# SCH_HallcurrentLA25p.net
KiCad netlist of a schematic drawn in Altium Designer
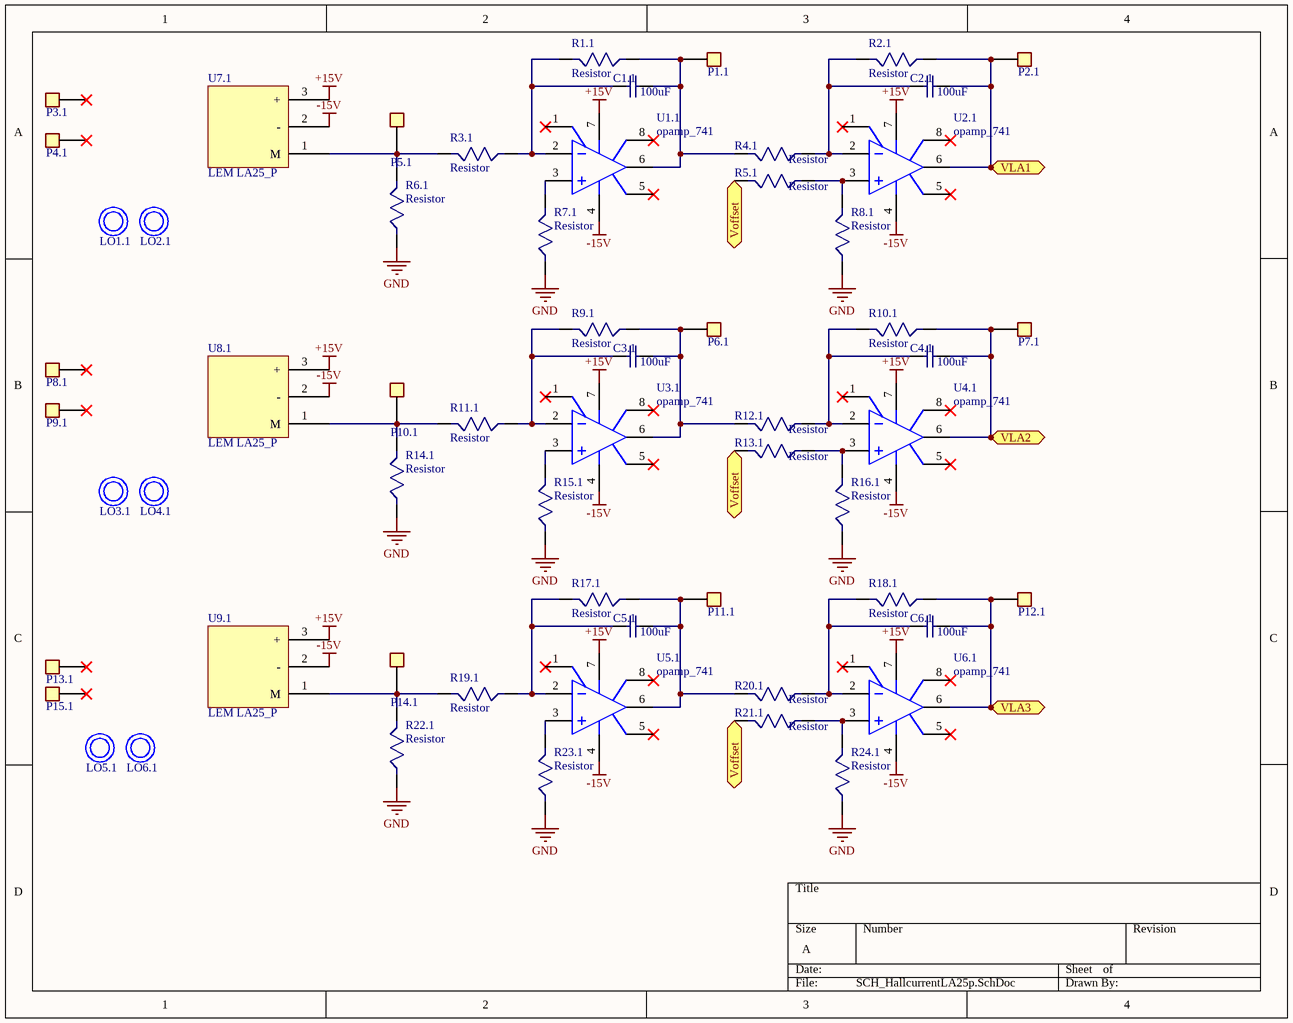
[diagram p0: SCH_HallcurrentLA25p.SchDoc]

(export (version "E")
  (design (tool "Eeschema 10.0.6"))
  (components
    (comp (ref "C1.1")
      (value "100uF")
      (footprint "CAPC0805")
      (description "capacitor non polar")
      (libsource (lib "thuvien_altium") (part "capacitor_non_polar"))
    )
    (comp (ref "C2.1")
      (value "100uF")
      (footprint "CAPC0805")
      (description "capacitor non polar")
      (libsource (lib "thuvien_altium") (part "capacitor_non_polar"))
    )
    (comp (ref "C3.1")
      (value "100uF")
      (footprint "CAPC0805")
      (description "capacitor non polar")
      (libsource (lib "thuvien_altium") (part "capacitor_non_polar"))
    )
    (comp (ref "C4.1")
      (value "100uF")
      (footprint "CAPC0805")
      (description "capacitor non polar")
      (libsource (lib "thuvien_altium") (part "capacitor_non_polar"))
    )
    (comp (ref "C5.1")
      (value "100uF")
      (footprint "CAPC0805")
      (description "capacitor non polar")
      (libsource (lib "thuvien_altium") (part "capacitor_non_polar"))
    )
    (comp (ref "C6.1")
      (value "100uF")
      (footprint "CAPC0805")
      (description "capacitor non polar")
      (libsource (lib "thuvien_altium") (part "capacitor_non_polar"))
    )
    (comp (ref "LO1.1")
      (value "LO KHOAN")
      (footprint "thuvien_altium:Lo Khoang - 6mm")
      (libsource (lib "thuvien_altium") (part "LO KHOAN"))
    )
    (comp (ref "LO2.1")
      (value "LO KHOAN")
      (footprint "thuvien_altium:Lo Khoang - 6mm")
      (libsource (lib "thuvien_altium") (part "LO KHOAN"))
    )
    (comp (ref "LO3.1")
      (value "LO KHOAN")
      (footprint "thuvien_altium:Lo Khoang - 6mm")
      (libsource (lib "thuvien_altium") (part "LO KHOAN"))
    )
    (comp (ref "LO4.1")
      (value "LO KHOAN")
      (footprint "thuvien_altium:Lo Khoang - 6mm")
      (libsource (lib "thuvien_altium") (part "LO KHOAN"))
    )
    (comp (ref "LO5.1")
      (value "LO KHOAN")
      (footprint "thuvien_altium:Lo Khoang - 6mm")
      (libsource (lib "thuvien_altium") (part "LO KHOAN"))
    )
    (comp (ref "LO6.1")
      (value "LO KHOAN")
      (footprint "thuvien_altium:Lo Khoang - 6mm")
      (libsource (lib "thuvien_altium") (part "LO KHOAN"))
    )
    (comp (ref "P1.1")
      (value "testpin")
      (footprint "thuvien_altium:Tp_blue_1p")
      (libsource (lib "thuvien_altium") (part "testpin"))
    )
    (comp (ref "P2.1")
      (value "testpin")
      (footprint "thuvien_altium:Tp_blue_1p")
      (libsource (lib "thuvien_altium") (part "testpin"))
    )
    (comp (ref "P3.1")
      (value "Terminal on PCB")
      (footprint "thuvien_altium:Terminal M5")
      (libsource (lib "thuvien_altium") (part "Terminal on PCB"))
    )
    (comp (ref "P4.1")
      (value "Terminal on PCB")
      (footprint "thuvien_altium:Terminal M5")
      (libsource (lib "thuvien_altium") (part "Terminal on PCB"))
    )
    (comp (ref "P5.1")
      (value "testpin")
      (footprint "thuvien_altium:Tp_blue_1p")
      (libsource (lib "") (part "testpin_1"))
    )
    (comp (ref "P6.1")
      (value "testpin")
      (footprint "thuvien_altium:Tp_blue_1p")
      (libsource (lib "thuvien_altium") (part "testpin"))
    )
    (comp (ref "P7.1")
      (value "testpin")
      (footprint "thuvien_altium:Tp_blue_1p")
      (libsource (lib "thuvien_altium") (part "testpin"))
    )
    (comp (ref "P8.1")
      (value "Terminal on PCB")
      (footprint "thuvien_altium:Terminal M5")
      (libsource (lib "thuvien_altium") (part "Terminal on PCB"))
    )
    (comp (ref "P9.1")
      (value "Terminal on PCB")
      (footprint "thuvien_altium:Terminal M5")
      (libsource (lib "thuvien_altium") (part "Terminal on PCB"))
    )
    (comp (ref "P10.1")
      (value "testpin")
      (footprint "thuvien_altium:Tp_blue_1p")
      (libsource (lib "") (part "testpin_1"))
    )
    (comp (ref "P11.1")
      (value "testpin")
      (footprint "thuvien_altium:Tp_blue_1p")
      (libsource (lib "thuvien_altium") (part "testpin"))
    )
    (comp (ref "P12.1")
      (value "testpin")
      (footprint "thuvien_altium:Tp_blue_1p")
      (libsource (lib "thuvien_altium") (part "testpin"))
    )
    (comp (ref "P13.1")
      (value "Terminal on PCB")
      (footprint "thuvien_altium:Terminal M5")
      (libsource (lib "thuvien_altium") (part "Terminal on PCB"))
    )
    (comp (ref "P14.1")
      (value "testpin")
      (footprint "thuvien_altium:Tp_blue_1p")
      (libsource (lib "") (part "testpin_1"))
    )
    (comp (ref "P15.1")
      (value "Terminal on PCB")
      (footprint "thuvien_altium:Terminal M5")
      (libsource (lib "thuvien_altium") (part "Terminal on PCB"))
    )
    (comp (ref "R1.1")
      (value "Resistor")
      (footprint "RESC0805")
      (description "resistor")
      (libsource (lib "thuvien_altium") (part "resistor"))
    )
    (comp (ref "R2.1")
      (value "Resistor")
      (footprint "RESC0805")
      (description "resistor")
      (libsource (lib "thuvien_altium") (part "resistor"))
    )
    (comp (ref "R3.1")
      (value "Resistor")
      (footprint "RESC0805")
      (description "resistor")
      (libsource (lib "thuvien_altium") (part "resistor"))
    )
    (comp (ref "R4.1")
      (value "Resistor")
      (footprint "RESC0805")
      (description "resistor")
      (libsource (lib "thuvien_altium") (part "resistor"))
    )
    (comp (ref "R5.1")
      (value "Resistor")
      (footprint "RESC0805")
      (description "resistor")
      (libsource (lib "thuvien_altium") (part "resistor"))
    )
    (comp (ref "R6.1")
      (value "Resistor")
      (footprint "RESC0805")
      (description "resistor")
      (libsource (lib "thuvien_altium") (part "resistor"))
    )
    (comp (ref "R7.1")
      (value "Resistor")
      (footprint "RESC0805")
      (description "resistor")
      (libsource (lib "thuvien_altium") (part "resistor"))
    )
    (comp (ref "R8.1")
      (value "Resistor")
      (footprint "RESC0805")
      (description "resistor")
      (libsource (lib "thuvien_altium") (part "resistor"))
    )
    (comp (ref "R9.1")
      (value "Resistor")
      (footprint "RESC0805")
      (description "resistor")
      (libsource (lib "thuvien_altium") (part "resistor"))
    )
    (comp (ref "R10.1")
      (value "Resistor")
      (footprint "RESC0805")
      (description "resistor")
      (libsource (lib "thuvien_altium") (part "resistor"))
    )
    (comp (ref "R11.1")
      (value "Resistor")
      (footprint "RESC0805")
      (description "resistor")
      (libsource (lib "thuvien_altium") (part "resistor"))
    )
    (comp (ref "R12.1")
      (value "Resistor")
      (footprint "RESC0805")
      (description "resistor")
      (libsource (lib "thuvien_altium") (part "resistor"))
    )
    (comp (ref "R13.1")
      (value "Resistor")
      (footprint "RESC0805")
      (description "resistor")
      (libsource (lib "thuvien_altium") (part "resistor"))
    )
    (comp (ref "R14.1")
      (value "Resistor")
      (footprint "RESC0805")
      (description "resistor")
      (libsource (lib "thuvien_altium") (part "resistor"))
    )
    (comp (ref "R15.1")
      (value "Resistor")
      (footprint "RESC0805")
      (description "resistor")
      (libsource (lib "thuvien_altium") (part "resistor"))
    )
    (comp (ref "R16.1")
      (value "Resistor")
      (footprint "RESC0805")
      (description "resistor")
      (libsource (lib "thuvien_altium") (part "resistor"))
    )
    (comp (ref "R17.1")
      (value "Resistor")
      (footprint "RESC0805")
      (description "resistor")
      (libsource (lib "thuvien_altium") (part "resistor"))
    )
    (comp (ref "R18.1")
      (value "Resistor")
      (footprint "RESC0805")
      (description "resistor")
      (libsource (lib "thuvien_altium") (part "resistor"))
    )
    (comp (ref "R19.1")
      (value "Resistor")
      (footprint "RESC0805")
      (description "resistor")
      (libsource (lib "thuvien_altium") (part "resistor"))
    )
    (comp (ref "R20.1")
      (value "Resistor")
      (footprint "RESC0805")
      (description "resistor")
      (libsource (lib "thuvien_altium") (part "resistor"))
    )
    (comp (ref "R21.1")
      (value "Resistor")
      (footprint "RESC0805")
      (description "resistor")
      (libsource (lib "thuvien_altium") (part "resistor"))
    )
    (comp (ref "R22.1")
      (value "Resistor")
      (footprint "RESC0805")
      (description "resistor")
      (libsource (lib "thuvien_altium") (part "resistor"))
    )
    (comp (ref "R23.1")
      (value "Resistor")
      (footprint "RESC0805")
      (description "resistor")
      (libsource (lib "thuvien_altium") (part "resistor"))
    )
    (comp (ref "R24.1")
      (value "Resistor")
      (footprint "RESC0805")
      (description "resistor")
      (libsource (lib "thuvien_altium") (part "resistor"))
    )
    (comp (ref "U1.1")
      (value "opamp_741")
      (footprint "thuvien_altium:SOIC-8_dan")
      (libsource (lib "thuvien_altium") (part "opamp 741"))
    )
    (comp (ref "U2.1")
      (value "opamp_741")
      (footprint "thuvien_altium:SOIC-8_dan")
      (libsource (lib "thuvien_altium") (part "opamp 741"))
    )
    (comp (ref "U3.1")
      (value "opamp_741")
      (footprint "thuvien_altium:SOIC-8_dan")
      (libsource (lib "thuvien_altium") (part "opamp 741"))
    )
    (comp (ref "U4.1")
      (value "opamp_741")
      (footprint "thuvien_altium:SOIC-8_dan")
      (libsource (lib "thuvien_altium") (part "opamp 741"))
    )
    (comp (ref "U5.1")
      (value "opamp_741")
      (footprint "thuvien_altium:SOIC-8_dan")
      (libsource (lib "thuvien_altium") (part "opamp 741"))
    )
    (comp (ref "U6.1")
      (value "opamp_741")
      (footprint "thuvien_altium:SOIC-8_dan")
      (libsource (lib "thuvien_altium") (part "opamp 741"))
    )
    (comp (ref "U7.1")
      (value "LEM LA25_P")
      (footprint "thuvien_altium:LEM LA25_P")
      (libsource (lib "thuvien_altium") (part "LEM LA25_P"))
    )
    (comp (ref "U8.1")
      (value "LEM LA25_P")
      (footprint "thuvien_altium:LEM LA25_P")
      (libsource (lib "thuvien_altium") (part "LEM LA25_P"))
    )
    (comp (ref "U9.1")
      (value "LEM LA25_P")
      (footprint "thuvien_altium:LEM LA25_P")
      (libsource (lib "thuvien_altium") (part "LEM LA25_P"))
    )
  )
  (nets
    (net (code "1") (name "+15V") (class "Default")
      (node (ref "U1.1") (pin "7") (pinfunction "V+_7") (pintype "power_in"))
      (node (ref "U2.1") (pin "7") (pinfunction "V+_7") (pintype "power_in"))
      (node (ref "U3.1") (pin "7") (pinfunction "V+_7") (pintype "power_in"))
      (node (ref "U4.1") (pin "7") (pinfunction "V+_7") (pintype "power_in"))
      (node (ref "U5.1") (pin "7") (pinfunction "V+_7") (pintype "power_in"))
      (node (ref "U6.1") (pin "7") (pinfunction "V+_7") (pintype "power_in"))
      (node (ref "U7.1") (pin "3") (pinfunction "+_3") (pintype "passive"))
      (node (ref "U8.1") (pin "3") (pinfunction "+_3") (pintype "passive"))
      (node (ref "U9.1") (pin "3") (pinfunction "+_3") (pintype "passive"))
    )
    (net (code "2") (name "-15V") (class "Default")
      (node (ref "U1.1") (pin "4") (pinfunction "V-_4") (pintype "power_in"))
      (node (ref "U2.1") (pin "4") (pinfunction "V-_4") (pintype "power_in"))
      (node (ref "U3.1") (pin "4") (pinfunction "V-_4") (pintype "power_in"))
      (node (ref "U4.1") (pin "4") (pinfunction "V-_4") (pintype "power_in"))
      (node (ref "U5.1") (pin "4") (pinfunction "V-_4") (pintype "power_in"))
      (node (ref "U6.1") (pin "4") (pinfunction "V-_4") (pintype "power_in"))
      (node (ref "U7.1") (pin "2") (pinfunction "-_2") (pintype "passive"))
      (node (ref "U8.1") (pin "2") (pinfunction "-_2") (pintype "passive"))
      (node (ref "U9.1") (pin "2") (pinfunction "-_2") (pintype "passive"))
    )
    (net (code "3") (name "/VLA1") (class "Default")
      (node (ref "C2.1") (pin "2") (pinfunction "2_2") (pintype "power_in"))
      (node (ref "P2.1") (pin "1") (pinfunction "1_1") (pintype "power_in"))
      (node (ref "R2.1") (pin "1") (pinfunction "1_1") (pintype "power_in"))
      (node (ref "U2.1") (pin "6") (pinfunction "OUT_6") (pintype "power_in"))
    )
    (net (code "4") (name "/VLA2") (class "Default")
      (node (ref "C4.1") (pin "2") (pinfunction "2_2") (pintype "power_in"))
      (node (ref "P7.1") (pin "1") (pinfunction "1_1") (pintype "power_in"))
      (node (ref "R10.1") (pin "1") (pinfunction "1_1") (pintype "power_in"))
      (node (ref "U4.1") (pin "6") (pinfunction "OUT_6") (pintype "power_in"))
    )
    (net (code "5") (name "/VLA3") (class "Default")
      (node (ref "C6.1") (pin "2") (pinfunction "2_2") (pintype "power_in"))
      (node (ref "P12.1") (pin "1") (pinfunction "1_1") (pintype "power_in"))
      (node (ref "R18.1") (pin "1") (pinfunction "1_1") (pintype "power_in"))
      (node (ref "U6.1") (pin "6") (pinfunction "OUT_6") (pintype "power_in"))
    )
    (net (code "6") (name "/Voffset") (class "Default")
      (node (ref "R13.1") (pin "2") (pinfunction "2_2") (pintype "power_in"))
      (node (ref "R21.1") (pin "2") (pinfunction "2_2") (pintype "power_in"))
      (node (ref "R5.1") (pin "2") (pinfunction "2_2") (pintype "power_in"))
    )
    (net (code "7") (name "GND") (class "Default")
      (node (ref "R14.1") (pin "1") (pinfunction "1_1") (pintype "power_in"))
      (node (ref "R15.1") (pin "1") (pinfunction "1_1") (pintype "power_in"))
      (node (ref "R16.1") (pin "1") (pinfunction "1_1") (pintype "power_in"))
      (node (ref "R22.1") (pin "1") (pinfunction "1_1") (pintype "power_in"))
      (node (ref "R23.1") (pin "1") (pinfunction "1_1") (pintype "power_in"))
      (node (ref "R24.1") (pin "1") (pinfunction "1_1") (pintype "power_in"))
      (node (ref "R6.1") (pin "1") (pinfunction "1_1") (pintype "power_in"))
      (node (ref "R7.1") (pin "1") (pinfunction "1_1") (pintype "power_in"))
      (node (ref "R8.1") (pin "1") (pinfunction "1_1") (pintype "power_in"))
    )
    (net (code "8") (name "Net-(U1.1-IN+)") (class "Default")
      (node (ref "R7.1") (pin "2") (pinfunction "2_2") (pintype "power_in"))
      (node (ref "U1.1") (pin "3") (pinfunction "IN+_3") (pintype "power_in"))
    )
    (net (code "9") (name "Net-(U1.1-IN-)") (class "Default")
      (node (ref "C1.1") (pin "1") (pinfunction "1_1") (pintype "power_in"))
      (node (ref "R1.1") (pin "2") (pinfunction "2_2") (pintype "power_in"))
      (node (ref "R3.1") (pin "1") (pinfunction "1_1") (pintype "power_in"))
      (node (ref "U1.1") (pin "2") (pinfunction "IN-_2") (pintype "power_in"))
    )
    (net (code "10") (name "Net-(U1.1-OUT)") (class "Default")
      (node (ref "C1.1") (pin "2") (pinfunction "2_2") (pintype "power_in"))
      (node (ref "P1.1") (pin "1") (pinfunction "1_1") (pintype "power_in"))
      (node (ref "R1.1") (pin "1") (pinfunction "1_1") (pintype "power_in"))
      (node (ref "R4.1") (pin "2") (pinfunction "2_2") (pintype "power_in"))
      (node (ref "U1.1") (pin "6") (pinfunction "OUT_6") (pintype "power_in"))
    )
    (net (code "11") (name "Net-(U2.1-IN+)") (class "Default")
      (node (ref "R5.1") (pin "1") (pinfunction "1_1") (pintype "power_in"))
      (node (ref "R8.1") (pin "2") (pinfunction "2_2") (pintype "power_in"))
      (node (ref "U2.1") (pin "3") (pinfunction "IN+_3") (pintype "power_in"))
    )
    (net (code "12") (name "Net-(U2.1-IN-)") (class "Default")
      (node (ref "C2.1") (pin "1") (pinfunction "1_1") (pintype "power_in"))
      (node (ref "R2.1") (pin "2") (pinfunction "2_2") (pintype "power_in"))
      (node (ref "R4.1") (pin "1") (pinfunction "1_1") (pintype "power_in"))
      (node (ref "U2.1") (pin "2") (pinfunction "IN-_2") (pintype "power_in"))
    )
    (net (code "13") (name "Net-(U3.1-IN+)") (class "Default")
      (node (ref "R15.1") (pin "2") (pinfunction "2_2") (pintype "power_in"))
      (node (ref "U3.1") (pin "3") (pinfunction "IN+_3") (pintype "power_in"))
    )
    (net (code "14") (name "Net-(U3.1-IN-)") (class "Default")
      (node (ref "C3.1") (pin "1") (pinfunction "1_1") (pintype "power_in"))
      (node (ref "R11.1") (pin "1") (pinfunction "1_1") (pintype "power_in"))
      (node (ref "R9.1") (pin "2") (pinfunction "2_2") (pintype "power_in"))
      (node (ref "U3.1") (pin "2") (pinfunction "IN-_2") (pintype "power_in"))
    )
    (net (code "15") (name "Net-(U3.1-OUT)") (class "Default")
      (node (ref "C3.1") (pin "2") (pinfunction "2_2") (pintype "power_in"))
      (node (ref "P6.1") (pin "1") (pinfunction "1_1") (pintype "power_in"))
      (node (ref "R12.1") (pin "2") (pinfunction "2_2") (pintype "power_in"))
      (node (ref "R9.1") (pin "1") (pinfunction "1_1") (pintype "power_in"))
      (node (ref "U3.1") (pin "6") (pinfunction "OUT_6") (pintype "power_in"))
    )
    (net (code "16") (name "Net-(U4.1-IN+)") (class "Default")
      (node (ref "R13.1") (pin "1") (pinfunction "1_1") (pintype "power_in"))
      (node (ref "R16.1") (pin "2") (pinfunction "2_2") (pintype "power_in"))
      (node (ref "U4.1") (pin "3") (pinfunction "IN+_3") (pintype "power_in"))
    )
    (net (code "17") (name "Net-(U4.1-IN-)") (class "Default")
      (node (ref "C4.1") (pin "1") (pinfunction "1_1") (pintype "power_in"))
      (node (ref "R10.1") (pin "2") (pinfunction "2_2") (pintype "power_in"))
      (node (ref "R12.1") (pin "1") (pinfunction "1_1") (pintype "power_in"))
      (node (ref "U4.1") (pin "2") (pinfunction "IN-_2") (pintype "power_in"))
    )
    (net (code "18") (name "Net-(U5.1-IN+)") (class "Default")
      (node (ref "R23.1") (pin "2") (pinfunction "2_2") (pintype "power_in"))
      (node (ref "U5.1") (pin "3") (pinfunction "IN+_3") (pintype "power_in"))
    )
    (net (code "19") (name "Net-(U5.1-IN-)") (class "Default")
      (node (ref "C5.1") (pin "1") (pinfunction "1_1") (pintype "power_in"))
      (node (ref "R17.1") (pin "2") (pinfunction "2_2") (pintype "power_in"))
      (node (ref "R19.1") (pin "1") (pinfunction "1_1") (pintype "power_in"))
      (node (ref "U5.1") (pin "2") (pinfunction "IN-_2") (pintype "power_in"))
    )
    (net (code "20") (name "Net-(U5.1-OUT)") (class "Default")
      (node (ref "C5.1") (pin "2") (pinfunction "2_2") (pintype "power_in"))
      (node (ref "P11.1") (pin "1") (pinfunction "1_1") (pintype "power_in"))
      (node (ref "R17.1") (pin "1") (pinfunction "1_1") (pintype "power_in"))
      (node (ref "R20.1") (pin "2") (pinfunction "2_2") (pintype "power_in"))
      (node (ref "U5.1") (pin "6") (pinfunction "OUT_6") (pintype "power_in"))
    )
    (net (code "21") (name "Net-(U6.1-IN+)") (class "Default")
      (node (ref "R21.1") (pin "1") (pinfunction "1_1") (pintype "power_in"))
      (node (ref "R24.1") (pin "2") (pinfunction "2_2") (pintype "power_in"))
      (node (ref "U6.1") (pin "3") (pinfunction "IN+_3") (pintype "power_in"))
    )
    (net (code "22") (name "Net-(U6.1-IN-)") (class "Default")
      (node (ref "C6.1") (pin "1") (pinfunction "1_1") (pintype "power_in"))
      (node (ref "R18.1") (pin "2") (pinfunction "2_2") (pintype "power_in"))
      (node (ref "R20.1") (pin "1") (pinfunction "1_1") (pintype "power_in"))
      (node (ref "U6.1") (pin "2") (pinfunction "IN-_2") (pintype "power_in"))
    )
    (net (code "23") (name "Net-(U7.1-M)") (class "Default")
      (node (ref "P5.1") (pin "1") (pinfunction "1_1") (pintype "power_in"))
      (node (ref "R3.1") (pin "2") (pinfunction "2_2") (pintype "power_in"))
      (node (ref "R6.1") (pin "2") (pinfunction "2_2") (pintype "power_in"))
      (node (ref "U7.1") (pin "1") (pinfunction "M_1") (pintype "passive"))
    )
    (net (code "24") (name "Net-(U8.1-M)") (class "Default")
      (node (ref "P10.1") (pin "1") (pinfunction "1_1") (pintype "power_in"))
      (node (ref "R11.1") (pin "2") (pinfunction "2_2") (pintype "power_in"))
      (node (ref "R14.1") (pin "2") (pinfunction "2_2") (pintype "power_in"))
      (node (ref "U8.1") (pin "1") (pinfunction "M_1") (pintype "passive"))
    )
    (net (code "25") (name "Net-(U9.1-M)") (class "Default")
      (node (ref "P14.1") (pin "1") (pinfunction "1_1") (pintype "power_in"))
      (node (ref "R19.1") (pin "2") (pinfunction "2_2") (pintype "power_in"))
      (node (ref "R22.1") (pin "2") (pinfunction "2_2") (pintype "power_in"))
      (node (ref "U9.1") (pin "1") (pinfunction "M_1") (pintype "passive"))
    )
    (net (code "26") (name "unconnected-(P3.1-Pad1)") (class "Default")
      (node (ref "P3.1") (pin "1") (pinfunction "1_1") (pintype "power_in+no_connect"))
    )
    (net (code "27") (name "unconnected-(P4.1-Pad1)") (class "Default")
      (node (ref "P4.1") (pin "1") (pinfunction "1_1") (pintype "power_in+no_connect"))
    )
    (net (code "28") (name "unconnected-(P8.1-Pad1)") (class "Default")
      (node (ref "P8.1") (pin "1") (pinfunction "1_1") (pintype "power_in+no_connect"))
    )
    (net (code "29") (name "unconnected-(P9.1-Pad1)") (class "Default")
      (node (ref "P9.1") (pin "1") (pinfunction "1_1") (pintype "power_in+no_connect"))
    )
    (net (code "30") (name "unconnected-(P13.1-Pad1)") (class "Default")
      (node (ref "P13.1") (pin "1") (pinfunction "1_1") (pintype "power_in+no_connect"))
    )
    (net (code "31") (name "unconnected-(P15.1-Pad1)") (class "Default")
      (node (ref "P15.1") (pin "1") (pinfunction "1_1") (pintype "power_in+no_connect"))
    )
    (net (code "32") (name "unconnected-(U1.1-NC-Pad5)") (class "Default")
      (node (ref "U1.1") (pin "5") (pinfunction "NC_5") (pintype "passive+no_connect"))
    )
    (net (code "33") (name "unconnected-(U1.1-VOSTRIM-Pad1)") (class "Default")
      (node (ref "U1.1") (pin "1") (pinfunction "VOSTRIM_1") (pintype "passive+no_connect"))
    )
    (net (code "34") (name "unconnected-(U1.1-VOSTRIM-Pad8)") (class "Default")
      (node (ref "U1.1") (pin "8") (pinfunction "VOSTRIM_8") (pintype "passive+no_connect"))
    )
    (net (code "35") (name "unconnected-(U2.1-NC-Pad5)") (class "Default")
      (node (ref "U2.1") (pin "5") (pinfunction "NC_5") (pintype "passive+no_connect"))
    )
    (net (code "36") (name "unconnected-(U2.1-VOSTRIM-Pad1)") (class "Default")
      (node (ref "U2.1") (pin "1") (pinfunction "VOSTRIM_1") (pintype "passive+no_connect"))
    )
    (net (code "37") (name "unconnected-(U2.1-VOSTRIM-Pad8)") (class "Default")
      (node (ref "U2.1") (pin "8") (pinfunction "VOSTRIM_8") (pintype "passive+no_connect"))
    )
    (net (code "38") (name "unconnected-(U3.1-NC-Pad5)") (class "Default")
      (node (ref "U3.1") (pin "5") (pinfunction "NC_5") (pintype "passive+no_connect"))
    )
    (net (code "39") (name "unconnected-(U3.1-VOSTRIM-Pad1)") (class "Default")
      (node (ref "U3.1") (pin "1") (pinfunction "VOSTRIM_1") (pintype "passive+no_connect"))
    )
    (net (code "40") (name "unconnected-(U3.1-VOSTRIM-Pad8)") (class "Default")
      (node (ref "U3.1") (pin "8") (pinfunction "VOSTRIM_8") (pintype "passive+no_connect"))
    )
    (net (code "41") (name "unconnected-(U4.1-NC-Pad5)") (class "Default")
      (node (ref "U4.1") (pin "5") (pinfunction "NC_5") (pintype "passive+no_connect"))
    )
    (net (code "42") (name "unconnected-(U4.1-VOSTRIM-Pad1)") (class "Default")
      (node (ref "U4.1") (pin "1") (pinfunction "VOSTRIM_1") (pintype "passive+no_connect"))
    )
    (net (code "43") (name "unconnected-(U4.1-VOSTRIM-Pad8)") (class "Default")
      (node (ref "U4.1") (pin "8") (pinfunction "VOSTRIM_8") (pintype "passive+no_connect"))
    )
    (net (code "44") (name "unconnected-(U5.1-NC-Pad5)") (class "Default")
      (node (ref "U5.1") (pin "5") (pinfunction "NC_5") (pintype "passive+no_connect"))
    )
    (net (code "45") (name "unconnected-(U5.1-VOSTRIM-Pad1)") (class "Default")
      (node (ref "U5.1") (pin "1") (pinfunction "VOSTRIM_1") (pintype "passive+no_connect"))
    )
    (net (code "46") (name "unconnected-(U5.1-VOSTRIM-Pad8)") (class "Default")
      (node (ref "U5.1") (pin "8") (pinfunction "VOSTRIM_8") (pintype "passive+no_connect"))
    )
    (net (code "47") (name "unconnected-(U6.1-NC-Pad5)") (class "Default")
      (node (ref "U6.1") (pin "5") (pinfunction "NC_5") (pintype "passive+no_connect"))
    )
    (net (code "48") (name "unconnected-(U6.1-VOSTRIM-Pad1)") (class "Default")
      (node (ref "U6.1") (pin "1") (pinfunction "VOSTRIM_1") (pintype "passive+no_connect"))
    )
    (net (code "49") (name "unconnected-(U6.1-VOSTRIM-Pad8)") (class "Default")
      (node (ref "U6.1") (pin "8") (pinfunction "VOSTRIM_8") (pintype "passive+no_connect"))
    )
  )
)
